# Beagle.net
KiCad netlist of a schematic drawn in Altium Designer
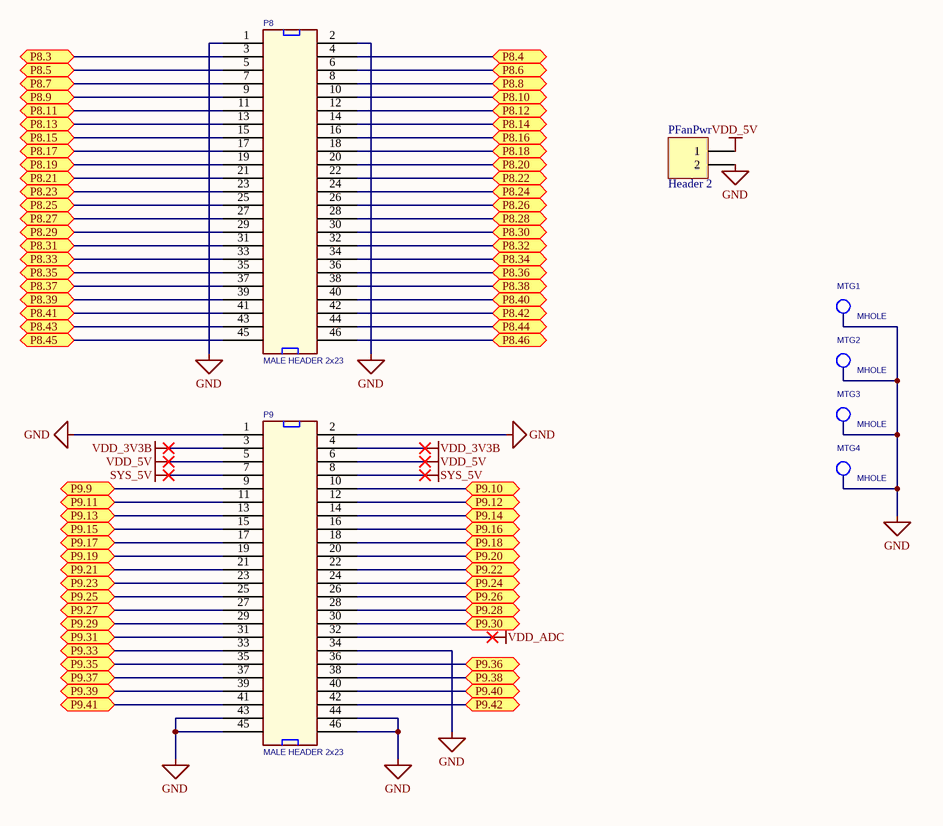
[diagram p0: Beagle.SchDoc]

(export (version "E")
  (design (tool "Eeschema 10.0.6"))
  (components
    (comp (ref "MTG1")
      (value "MHOLE")
      (footprint "MTGH200C125D_PL")
      (libsource (lib "BEAGLEBONEBLACK_REV A5B") (part "MHOLE"))
    )
    (comp (ref "MTG2")
      (value "MHOLE")
      (footprint "MTGH200C125D_PL")
      (libsource (lib "BEAGLEBONEBLACK_REV A5B") (part "MHOLE"))
    )
    (comp (ref "MTG3")
      (value "MHOLE")
      (footprint "MTGH200C125D_PL")
      (libsource (lib "BEAGLEBONEBLACK_REV A5B") (part "MHOLE"))
    )
    (comp (ref "MTG4")
      (value "MHOLE")
      (footprint "MTGH200C125D_PL")
      (libsource (lib "BEAGLEBONEBLACK_REV A5B") (part "MHOLE"))
    )
    (comp (ref "P8")
      (value "MALE HEADER 2x23")
      (description "CONN HEADER FMAL 46PS.1\" DL GOLD")
      (fields (field (name "MANUFACTURER") "Sullins Connector Solutions"))
      (libsource (lib "BEAGLEBONEBLACK_REV A5B") (part "HDR_46_F_2_0.1_0.1"))
    )
    (comp (ref "P9")
      (value "MALE HEADER 2x23")
      (description "CONN HEADER FMAL 46PS.1\" DL GOLD")
      (fields (field (name "MANUFACTURER") "Sullins Connector Solutions"))
      (libsource (lib "BEAGLEBONEBLACK_REV A5B") (part "HDR_46_F_2_0.1_0.1"))
    )
    (comp (ref "PFanPwr")
      (value "Header 2")
      (footprint "HDR1X2")
      (description "Header, 2-Pin")
      (fields (field (name "PUBLISHER") "Altium Limited"))
      (libsource (lib "Miscellaneous Connectors") (part "Header 2"))
    )
  )
  (nets
    (net (code "1") (name "/P8.3") (class "Default")
      (node (ref "P8") (pin "3") (pinfunction "2_3") (pintype "passive"))
    )
    (net (code "2") (name "/P8.4") (class "Default")
      (node (ref "P8") (pin "4") (pinfunction "27_4") (pintype "passive"))
    )
    (net (code "3") (name "/P8.5") (class "Default")
      (node (ref "P8") (pin "5") (pinfunction "3_5") (pintype "passive"))
    )
    (net (code "4") (name "/P8.6") (class "Default")
      (node (ref "P8") (pin "6") (pinfunction "28_6") (pintype "passive"))
    )
    (net (code "5") (name "/P8.7") (class "Default")
      (node (ref "P8") (pin "7") (pinfunction "4_7") (pintype "passive"))
    )
    (net (code "6") (name "/P8.8") (class "Default")
      (node (ref "P8") (pin "8") (pinfunction "29_8") (pintype "passive"))
    )
    (net (code "7") (name "/P8.9") (class "Default")
      (node (ref "P8") (pin "9") (pinfunction "5_9") (pintype "passive"))
    )
    (net (code "8") (name "/P8.10") (class "Default")
      (node (ref "P8") (pin "10") (pinfunction "30_10") (pintype "passive"))
    )
    (net (code "9") (name "/P8.11") (class "Default")
      (node (ref "P8") (pin "11") (pinfunction "6_11") (pintype "passive"))
    )
    (net (code "10") (name "/P8.12") (class "Default")
      (node (ref "P8") (pin "12") (pinfunction "31_12") (pintype "passive"))
    )
    (net (code "11") (name "/P8.13") (class "Default")
      (node (ref "P8") (pin "13") (pinfunction "7_13") (pintype "passive"))
    )
    (net (code "12") (name "/P8.14") (class "Default")
      (node (ref "P8") (pin "14") (pinfunction "32_14") (pintype "passive"))
    )
    (net (code "13") (name "/P8.15") (class "Default")
      (node (ref "P8") (pin "15") (pinfunction "8_15") (pintype "passive"))
    )
    (net (code "14") (name "/P8.16") (class "Default")
      (node (ref "P8") (pin "16") (pinfunction "33_16") (pintype "passive"))
    )
    (net (code "15") (name "/P8.17") (class "Default")
      (node (ref "P8") (pin "17") (pinfunction "9_17") (pintype "passive"))
    )
    (net (code "16") (name "/P8.18") (class "Default")
      (node (ref "P8") (pin "18") (pinfunction "34_18") (pintype "passive"))
    )
    (net (code "17") (name "/P8.19") (class "Default")
      (node (ref "P8") (pin "19") (pinfunction "10_19") (pintype "passive"))
    )
    (net (code "18") (name "/P8.20") (class "Default")
      (node (ref "P8") (pin "20") (pinfunction "35_20") (pintype "passive"))
    )
    (net (code "19") (name "/P8.21") (class "Default")
      (node (ref "P8") (pin "21") (pinfunction "11_21") (pintype "passive"))
    )
    (net (code "20") (name "/P8.22") (class "Default")
      (node (ref "P8") (pin "22") (pinfunction "36_22") (pintype "passive"))
    )
    (net (code "21") (name "/P8.23") (class "Default")
      (node (ref "P8") (pin "23") (pinfunction "12_23") (pintype "passive"))
    )
    (net (code "22") (name "/P8.24") (class "Default")
      (node (ref "P8") (pin "24") (pinfunction "37_24") (pintype "passive"))
    )
    (net (code "23") (name "/P8.25") (class "Default")
      (node (ref "P8") (pin "25") (pinfunction "13_25") (pintype "passive"))
    )
    (net (code "24") (name "/P8.26") (class "Default")
      (node (ref "P8") (pin "26") (pinfunction "38_26") (pintype "passive"))
    )
    (net (code "25") (name "/P8.27") (class "Default")
      (node (ref "P8") (pin "27") (pinfunction "14_27") (pintype "passive"))
    )
    (net (code "26") (name "/P8.28") (class "Default")
      (node (ref "P8") (pin "28") (pinfunction "39_28") (pintype "passive"))
    )
    (net (code "27") (name "/P8.29") (class "Default")
      (node (ref "P8") (pin "29") (pinfunction "15_29") (pintype "passive"))
    )
    (net (code "28") (name "/P8.30") (class "Default")
      (node (ref "P8") (pin "30") (pinfunction "40_30") (pintype "passive"))
    )
    (net (code "29") (name "/P8.31") (class "Default")
      (node (ref "P8") (pin "31") (pinfunction "16_31") (pintype "passive"))
    )
    (net (code "30") (name "/P8.32") (class "Default")
      (node (ref "P8") (pin "32") (pinfunction "41_32") (pintype "passive"))
    )
    (net (code "31") (name "/P8.33") (class "Default")
      (node (ref "P8") (pin "33") (pinfunction "17_33") (pintype "passive"))
    )
    (net (code "32") (name "/P8.34") (class "Default")
      (node (ref "P8") (pin "34") (pinfunction "42_34") (pintype "passive"))
    )
    (net (code "33") (name "/P8.35") (class "Default")
      (node (ref "P8") (pin "35") (pinfunction "18_35") (pintype "passive"))
    )
    (net (code "34") (name "/P8.36") (class "Default")
      (node (ref "P8") (pin "36") (pinfunction "43_36") (pintype "passive"))
    )
    (net (code "35") (name "/P8.37") (class "Default")
      (node (ref "P8") (pin "37") (pinfunction "19_37") (pintype "passive"))
    )
    (net (code "36") (name "/P8.38") (class "Default")
      (node (ref "P8") (pin "38") (pinfunction "44_38") (pintype "passive"))
    )
    (net (code "37") (name "/P8.39") (class "Default")
      (node (ref "P8") (pin "39") (pinfunction "20_39") (pintype "passive"))
    )
    (net (code "38") (name "/P8.40") (class "Default")
      (node (ref "P8") (pin "40") (pinfunction "45_40") (pintype "passive"))
    )
    (net (code "39") (name "/P8.41") (class "Default")
      (node (ref "P8") (pin "41") (pinfunction "21_41") (pintype "passive"))
    )
    (net (code "40") (name "/P8.42") (class "Default")
      (node (ref "P8") (pin "42") (pinfunction "46_42") (pintype "passive"))
    )
    (net (code "41") (name "/P8.43") (class "Default")
      (node (ref "P8") (pin "43") (pinfunction "22_43") (pintype "passive"))
    )
    (net (code "42") (name "/P8.44") (class "Default")
      (node (ref "P8") (pin "44") (pinfunction "47_44") (pintype "passive"))
    )
    (net (code "43") (name "/P8.45") (class "Default")
      (node (ref "P8") (pin "45") (pinfunction "23_45") (pintype "passive"))
    )
    (net (code "44") (name "/P8.46") (class "Default")
      (node (ref "P8") (pin "46") (pinfunction "48_46") (pintype "passive"))
    )
    (net (code "45") (name "/P9.9") (class "Default")
      (node (ref "P9") (pin "9") (pinfunction "5_9") (pintype "passive"))
    )
    (net (code "46") (name "/P9.10") (class "Default")
      (node (ref "P9") (pin "10") (pinfunction "30_10") (pintype "passive"))
    )
    (net (code "47") (name "/P9.11") (class "Default")
      (node (ref "P9") (pin "11") (pinfunction "6_11") (pintype "passive"))
    )
    (net (code "48") (name "/P9.12") (class "Default")
      (node (ref "P9") (pin "12") (pinfunction "31_12") (pintype "passive"))
    )
    (net (code "49") (name "/P9.13") (class "Default")
      (node (ref "P9") (pin "13") (pinfunction "7_13") (pintype "passive"))
    )
    (net (code "50") (name "/P9.14") (class "Default")
      (node (ref "P9") (pin "14") (pinfunction "32_14") (pintype "passive"))
    )
    (net (code "51") (name "/P9.15") (class "Default")
      (node (ref "P9") (pin "15") (pinfunction "8_15") (pintype "passive"))
    )
    (net (code "52") (name "/P9.16") (class "Default")
      (node (ref "P9") (pin "16") (pinfunction "33_16") (pintype "passive"))
    )
    (net (code "53") (name "/P9.17") (class "Default")
      (node (ref "P9") (pin "17") (pinfunction "9_17") (pintype "passive"))
    )
    (net (code "54") (name "/P9.18") (class "Default")
      (node (ref "P9") (pin "18") (pinfunction "34_18") (pintype "passive"))
    )
    (net (code "55") (name "/P9.19") (class "Default")
      (node (ref "P9") (pin "19") (pinfunction "10_19") (pintype "passive"))
    )
    (net (code "56") (name "/P9.20") (class "Default")
      (node (ref "P9") (pin "20") (pinfunction "35_20") (pintype "passive"))
    )
    (net (code "57") (name "/P9.21") (class "Default")
      (node (ref "P9") (pin "21") (pinfunction "11_21") (pintype "passive"))
    )
    (net (code "58") (name "/P9.22") (class "Default")
      (node (ref "P9") (pin "22") (pinfunction "36_22") (pintype "passive"))
    )
    (net (code "59") (name "/P9.23") (class "Default")
      (node (ref "P9") (pin "23") (pinfunction "12_23") (pintype "passive"))
    )
    (net (code "60") (name "/P9.24") (class "Default")
      (node (ref "P9") (pin "24") (pinfunction "37_24") (pintype "passive"))
    )
    (net (code "61") (name "/P9.25") (class "Default")
      (node (ref "P9") (pin "25") (pinfunction "13_25") (pintype "passive"))
    )
    (net (code "62") (name "/P9.26") (class "Default")
      (node (ref "P9") (pin "26") (pinfunction "38_26") (pintype "passive"))
    )
    (net (code "63") (name "/P9.27") (class "Default")
      (node (ref "P9") (pin "27") (pinfunction "14_27") (pintype "passive"))
    )
    (net (code "64") (name "/P9.28") (class "Default")
      (node (ref "P9") (pin "28") (pinfunction "39_28") (pintype "passive"))
    )
    (net (code "65") (name "/P9.29") (class "Default")
      (node (ref "P9") (pin "29") (pinfunction "15_29") (pintype "passive"))
    )
    (net (code "66") (name "/P9.30") (class "Default")
      (node (ref "P9") (pin "30") (pinfunction "40_30") (pintype "passive"))
    )
    (net (code "67") (name "/P9.31") (class "Default")
      (node (ref "P9") (pin "31") (pinfunction "16_31") (pintype "passive"))
    )
    (net (code "68") (name "/P9.33") (class "Default")
      (node (ref "P9") (pin "33") (pinfunction "17_33") (pintype "passive"))
    )
    (net (code "69") (name "/P9.35") (class "Default")
      (node (ref "P9") (pin "35") (pinfunction "18_35") (pintype "passive"))
    )
    (net (code "70") (name "/P9.36") (class "Default")
      (node (ref "P9") (pin "36") (pinfunction "43_36") (pintype "passive"))
    )
    (net (code "71") (name "/P9.37") (class "Default")
      (node (ref "P9") (pin "37") (pinfunction "19_37") (pintype "passive"))
    )
    (net (code "72") (name "/P9.38") (class "Default")
      (node (ref "P9") (pin "38") (pinfunction "44_38") (pintype "passive"))
    )
    (net (code "73") (name "/P9.39") (class "Default")
      (node (ref "P9") (pin "39") (pinfunction "20_39") (pintype "passive"))
    )
    (net (code "74") (name "/P9.40") (class "Default")
      (node (ref "P9") (pin "40") (pinfunction "45_40") (pintype "passive"))
    )
    (net (code "75") (name "/P9.41") (class "Default")
      (node (ref "P9") (pin "41") (pinfunction "21_41") (pintype "passive"))
    )
    (net (code "76") (name "/P9.42") (class "Default")
      (node (ref "P9") (pin "42") (pinfunction "46_42") (pintype "passive"))
    )
    (net (code "77") (name "GND") (class "Default")
      (node (ref "MTG1") (pin "1") (pinfunction "TP_1") (pintype "passive"))
      (node (ref "MTG2") (pin "1") (pinfunction "TP_1") (pintype "passive"))
      (node (ref "MTG3") (pin "1") (pinfunction "TP_1") (pintype "passive"))
      (node (ref "MTG4") (pin "1") (pinfunction "TP_1") (pintype "passive"))
      (node (ref "P8") (pin "1") (pinfunction "1_1") (pintype "passive"))
      (node (ref "P8") (pin "2") (pinfunction "26_2") (pintype "passive"))
      (node (ref "P9") (pin "1") (pinfunction "1_1") (pintype "passive"))
      (node (ref "P9") (pin "2") (pinfunction "26_2") (pintype "passive"))
      (node (ref "P9") (pin "34") (pinfunction "42_34") (pintype "passive"))
      (node (ref "P9") (pin "43") (pinfunction "22_43") (pintype "passive"))
      (node (ref "P9") (pin "44") (pinfunction "47_44") (pintype "passive"))
      (node (ref "P9") (pin "45") (pinfunction "23_45") (pintype "passive"))
      (node (ref "P9") (pin "46") (pinfunction "48_46") (pintype "passive"))
      (node (ref "PFanPwr") (pin "2") (pinfunction "2_2") (pintype "passive"))
    )
    (net (code "78") (name "SYS_5V") (class "Default")
      (node (ref "P9") (pin "7") (pinfunction "4_7") (pintype "passive"))
      (node (ref "P9") (pin "8") (pinfunction "29_8") (pintype "passive"))
    )
    (net (code "79") (name "VDD_3V3B") (class "Default")
      (node (ref "P9") (pin "3") (pinfunction "2_3") (pintype "passive"))
      (node (ref "P9") (pin "4") (pinfunction "27_4") (pintype "passive"))
    )
    (net (code "80") (name "VDD_5V") (class "Default")
      (node (ref "P9") (pin "5") (pinfunction "3_5") (pintype "passive"))
      (node (ref "P9") (pin "6") (pinfunction "28_6") (pintype "passive"))
      (node (ref "PFanPwr") (pin "1") (pinfunction "1_1") (pintype "passive"))
    )
    (net (code "81") (name "VDD_ADC") (class "Default")
      (node (ref "P9") (pin "32") (pinfunction "41_32") (pintype "passive"))
    )
  )
)
